# pcb_schematic.net
KiCad netlist of a schematic drawn in EAGLE
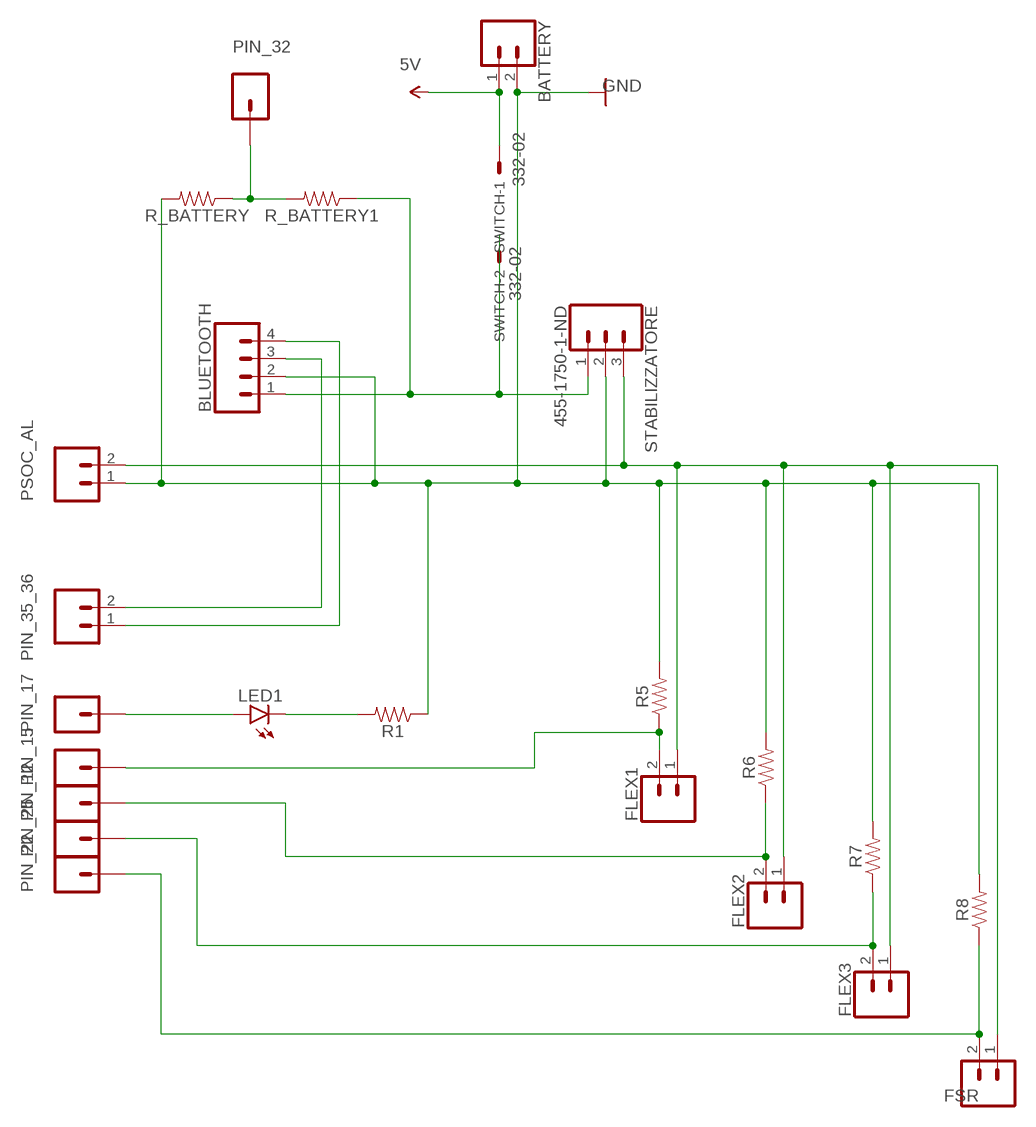
[diagram p0: schematic, sheet 1]

(export (version "E")
  (design (tool "Eeschema 10.0.6"))
  (components
    (comp (ref "BATTERY")
      (value "CONN_02")
      (footprint "eagle-import:1X02")
      (libsource (lib "eagle-import") (part "CONN_02"))
    )
    (comp (ref "BLUETOOTH")
      (value "CONN_04")
      (footprint "eagle-import:1X04")
      (libsource (lib "eagle-import") (part "CONN_04"))
    )
    (comp (ref "FLEX1")
      (value "CONN_02")
      (footprint "eagle-import:1X02")
      (libsource (lib "eagle-import") (part "CONN_02"))
    )
    (comp (ref "FLEX2")
      (value "CONN_02")
      (footprint "eagle-import:1X02")
      (libsource (lib "eagle-import") (part "CONN_02"))
    )
    (comp (ref "FLEX3")
      (value "CONN_02")
      (footprint "eagle-import:1X02")
      (libsource (lib "eagle-import") (part "CONN_02"))
    )
    (comp (ref "FSR")
      (value "CONN_02")
      (footprint "eagle-import:1X02")
      (libsource (lib "eagle-import") (part "CONN_02"))
    )
    (comp (ref "LED1")
      (value "LED5MM")
      (footprint "eagle-import:LED5MM")
      (libsource (lib "eagle-import") (part "LED5MM"))
    )
    (comp (ref "PIN_12")
      (value "CONN_01")
      (footprint "eagle-import:1X01")
      (libsource (lib "eagle-import") (part "CONN_01"))
    )
    (comp (ref "PIN_15")
      (value "CONN_01")
      (footprint "eagle-import:1X01")
      (libsource (lib "eagle-import") (part "CONN_01"))
    )
    (comp (ref "PIN_17")
      (value "CONN_01")
      (footprint "eagle-import:1X01")
      (libsource (lib "eagle-import") (part "CONN_01"))
    )
    (comp (ref "PIN_22")
      (value "CONN_01")
      (footprint "eagle-import:1X01")
      (libsource (lib "eagle-import") (part "CONN_01"))
    )
    (comp (ref "PIN_25")
      (value "CONN_01")
      (footprint "eagle-import:1X01")
      (libsource (lib "eagle-import") (part "CONN_01"))
    )
    (comp (ref "PIN_32")
      (value "CONN_01")
      (footprint "eagle-import:1X01")
      (libsource (lib "eagle-import") (part "CONN_01"))
    )
    (comp (ref "PIN_35_36")
      (value "CONN_02")
      (footprint "eagle-import:1X02")
      (libsource (lib "eagle-import") (part "CONN_02"))
    )
    (comp (ref "PSOC_AL")
      (value "CONN_02")
      (footprint "eagle-import:1X02")
      (libsource (lib "eagle-import") (part "CONN_02"))
    )
    (comp (ref "R1")
      (value "RESISTORAXIAL-0.3")
      (footprint "eagle-import:AXIAL-0.3")
      (libsource (lib "eagle-import") (part "RESISTORAXIAL-0.3"))
    )
    (comp (ref "R5")
      (value "RESISTORAXIAL-0.3")
      (footprint "eagle-import:AXIAL-0.3")
      (libsource (lib "eagle-import") (part "RESISTORAXIAL-0.3"))
    )
    (comp (ref "R6")
      (value "RESISTORAXIAL-0.3")
      (footprint "eagle-import:AXIAL-0.3")
      (libsource (lib "eagle-import") (part "RESISTORAXIAL-0.3"))
    )
    (comp (ref "R7")
      (value "RESISTORAXIAL-0.3")
      (footprint "eagle-import:AXIAL-0.3")
      (libsource (lib "eagle-import") (part "RESISTORAXIAL-0.3"))
    )
    (comp (ref "R8")
      (value "RESISTORAXIAL-0.3")
      (footprint "eagle-import:AXIAL-0.3")
      (libsource (lib "eagle-import") (part "RESISTORAXIAL-0.3"))
    )
    (comp (ref "R_BATTERY")
      (value "RESISTORAXIAL-0.3")
      (footprint "eagle-import:AXIAL-0.3")
      (libsource (lib "eagle-import") (part "RESISTORAXIAL-0.3"))
    )
    (comp (ref "R_BATTERY1")
      (value "RESISTORAXIAL-0.3")
      (footprint "eagle-import:AXIAL-0.3")
      (libsource (lib "eagle-import") (part "RESISTORAXIAL-0.3"))
    )
    (comp (ref "STABILIZZATORE")
      (value "455-1750-1-ND")
      (footprint "eagle-import:1X03")
      (libsource (lib "eagle-import") (part "CONN_03"))
    )
    (comp (ref "SWITCH")
      (value "332-02")
      (footprint "eagle-import:332-02")
      (libsource (lib "eagle-import") (part "332-02"))
    )
  )
  (nets
    (net (code "1") (name "5V") (class "Default")
      (node (ref "BATTERY") (pin "1") (pinfunction "1_1") (pintype "passive"))
      (node (ref "SWITCH") (pin "1") (pinfunction "S_1") (pintype "passive"))
    )
    (net (code "2") (name "GND") (class "Default")
      (node (ref "BATTERY") (pin "2") (pinfunction "2_2") (pintype "passive"))
      (node (ref "BLUETOOTH") (pin "2") (pinfunction "2_2") (pintype "passive"))
      (node (ref "PSOC_AL") (pin "1") (pinfunction "1_1") (pintype "passive"))
      (node (ref "R1") (pin "P$1") (pinfunction "1_P$1") (pintype "passive"))
      (node (ref "R5") (pin "P$2") (pinfunction "2_P$2") (pintype "passive"))
      (node (ref "R6") (pin "P$2") (pinfunction "2_P$2") (pintype "passive"))
      (node (ref "R7") (pin "P$2") (pinfunction "2_P$2") (pintype "passive"))
      (node (ref "R8") (pin "P$2") (pinfunction "2_P$2") (pintype "passive"))
      (node (ref "R_BATTERY") (pin "P$2") (pinfunction "2_P$2") (pintype "passive"))
      (node (ref "STABILIZZATORE") (pin "2") (pinfunction "2_2") (pintype "passive"))
    )
    (net (code "3") (name "Net-(BLUETOOTH-Pad3)") (class "Default")
      (node (ref "BLUETOOTH") (pin "3") (pinfunction "3_3") (pintype "passive"))
      (node (ref "PIN_35_36") (pin "2") (pinfunction "2_2") (pintype "passive"))
    )
    (net (code "4") (name "Net-(BLUETOOTH-Pad4)") (class "Default")
      (node (ref "BLUETOOTH") (pin "4") (pinfunction "4_4") (pintype "passive"))
      (node (ref "PIN_35_36") (pin "1") (pinfunction "1_1") (pintype "passive"))
    )
    (net (code "5") (name "Net-(FLEX1-Pad1)") (class "Default")
      (node (ref "FLEX1") (pin "1") (pinfunction "1_1") (pintype "passive"))
      (node (ref "FLEX2") (pin "1") (pinfunction "1_1") (pintype "passive"))
      (node (ref "FLEX3") (pin "1") (pinfunction "1_1") (pintype "passive"))
      (node (ref "FSR") (pin "1") (pinfunction "1_1") (pintype "passive"))
      (node (ref "PSOC_AL") (pin "2") (pinfunction "2_2") (pintype "passive"))
      (node (ref "STABILIZZATORE") (pin "3") (pinfunction "3_3") (pintype "passive"))
    )
    (net (code "6") (name "Net-(LED1-C)") (class "Default")
      (node (ref "LED1") (pin "K") (pinfunction "C_K") (pintype "passive"))
      (node (ref "R1") (pin "P$2") (pinfunction "2_P$2") (pintype "passive"))
    )
    (net (code "7") (name "Net-(LED1-PadA)") (class "Default")
      (node (ref "LED1") (pin "A") (pinfunction "A_A") (pintype "passive"))
      (node (ref "PIN_17") (pin "1") (pinfunction "1_1") (pintype "passive"))
    )
    (net (code "8") (name "Net-(R5-1)") (class "Default")
      (node (ref "FLEX1") (pin "2") (pinfunction "2_2") (pintype "passive"))
      (node (ref "PIN_15") (pin "1") (pinfunction "1_1") (pintype "passive"))
      (node (ref "R5") (pin "P$1") (pinfunction "1_P$1") (pintype "passive"))
    )
    (net (code "9") (name "Net-(R6-1)") (class "Default")
      (node (ref "FLEX2") (pin "2") (pinfunction "2_2") (pintype "passive"))
      (node (ref "PIN_12") (pin "1") (pinfunction "1_1") (pintype "passive"))
      (node (ref "R6") (pin "P$1") (pinfunction "1_P$1") (pintype "passive"))
    )
    (net (code "10") (name "Net-(R7-1)") (class "Default")
      (node (ref "FLEX3") (pin "2") (pinfunction "2_2") (pintype "passive"))
      (node (ref "PIN_25") (pin "1") (pinfunction "1_1") (pintype "passive"))
      (node (ref "R7") (pin "P$1") (pinfunction "1_P$1") (pintype "passive"))
    )
    (net (code "11") (name "Net-(R8-1)") (class "Default")
      (node (ref "FSR") (pin "2") (pinfunction "2_2") (pintype "passive"))
      (node (ref "PIN_22") (pin "1") (pinfunction "1_1") (pintype "passive"))
      (node (ref "R8") (pin "P$1") (pinfunction "1_P$1") (pintype "passive"))
    )
    (net (code "12") (name "Net-(R_BATTERY-1)") (class "Default")
      (node (ref "PIN_32") (pin "1") (pinfunction "1_1") (pintype "passive"))
      (node (ref "R_BATTERY") (pin "P$1") (pinfunction "1_P$1") (pintype "passive"))
      (node (ref "R_BATTERY1") (pin "P$2") (pinfunction "2_P$2") (pintype "passive"))
    )
    (net (code "13") (name "Net-(R_BATTERY1-1)") (class "Default")
      (node (ref "BLUETOOTH") (pin "1") (pinfunction "1_1") (pintype "passive"))
      (node (ref "R_BATTERY1") (pin "P$1") (pinfunction "1_P$1") (pintype "passive"))
      (node (ref "STABILIZZATORE") (pin "1") (pinfunction "1_1") (pintype "passive"))
      (node (ref "SWITCH") (pin "2") (pinfunction "S_2") (pintype "passive"))
    )
  )
)
